# Superseal.net
KiCad netlist of a schematic drawn in Altium Designer
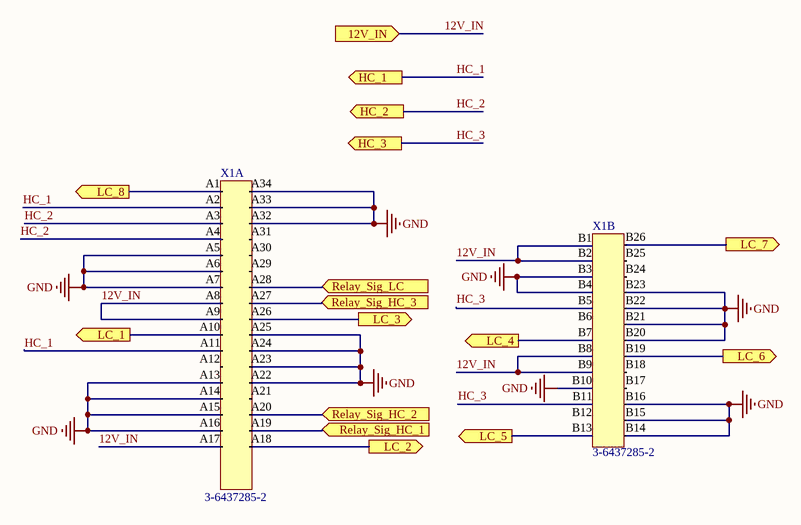
[diagram p0: Superseal.SchDoc]

(export (version "E")
  (design (tool "Eeschema 10.0.6"))
  (components
    (comp (ref "X1")
      (value "3-6437285-2")
      (footprint "SUPERSEAL 60POS 90Deg")
      (description "90 Degree")
      (libsource (lib "Altium-Lib") (part "CONN Superseal 60POS"))
    )
  )
  (nets
    (net (code "1") (name "/12V_IN") (class "Default")
      (node (ref "X1") (pin "A17") (pintype "bidirectional"))
      (node (ref "X1") (pin "A8") (pintype "bidirectional"))
      (node (ref "X1") (pin "A9") (pintype "bidirectional"))
      (node (ref "X1") (pin "B1") (pintype "bidirectional"))
      (node (ref "X1") (pin "B2") (pintype "bidirectional"))
      (node (ref "X1") (pin "B8") (pintype "bidirectional"))
      (node (ref "X1") (pin "B9") (pintype "bidirectional"))
    )
    (net (code "2") (name "/HC_1") (class "Default")
      (node (ref "X1") (pin "A11") (pintype "bidirectional"))
      (node (ref "X1") (pin "A2") (pintype "bidirectional"))
    )
    (net (code "3") (name "/HC_2") (class "Default")
      (node (ref "X1") (pin "A3") (pintype "bidirectional"))
      (node (ref "X1") (pin "A4") (pintype "bidirectional"))
    )
    (net (code "4") (name "/HC_3") (class "Default")
      (node (ref "X1") (pin "B11") (pintype "bidirectional"))
      (node (ref "X1") (pin "B5") (pintype "bidirectional"))
    )
    (net (code "5") (name "/LC_1") (class "Default") (node (ref "X1") (pin "A10") (pintype "bidirectional")))
    (net (code "6") (name "/LC_2") (class "Default") (node (ref "X1") (pin "A18") (pintype "bidirectional")))
    (net (code "7") (name "/LC_3") (class "Default") (node (ref "X1") (pin "A26") (pintype "bidirectional")))
    (net (code "8") (name "/LC_4") (class "Default") (node (ref "X1") (pin "B7") (pintype "bidirectional")))
    (net (code "9") (name "/LC_5") (class "Default") (node (ref "X1") (pin "B13") (pintype "bidirectional")))
    (net (code "10") (name "/LC_6") (class "Default") (node (ref "X1") (pin "B19") (pintype "bidirectional")))
    (net (code "11") (name "/LC_7") (class "Default") (node (ref "X1") (pin "B26") (pintype "bidirectional")))
    (net (code "12") (name "/LC_8") (class "Default") (node (ref "X1") (pin "A1") (pintype "bidirectional")))
    (net (code "13") (name "/Relay_Sig_HC_1") (class "Default")
      (node (ref "X1") (pin "A19") (pintype "bidirectional"))
    )
    (net (code "14") (name "/Relay_Sig_HC_2") (class "Default")
      (node (ref "X1") (pin "A20") (pintype "bidirectional"))
    )
    (net (code "15") (name "/Relay_Sig_HC_3") (class "Default")
      (node (ref "X1") (pin "A27") (pintype "bidirectional"))
    )
    (net (code "16") (name "/Relay_Sig_LC") (class "Default")
      (node (ref "X1") (pin "A28") (pintype "bidirectional"))
    )
    (net (code "17") (name "GND") (class "Default")
      (node (ref "X1") (pin "A13") (pintype "bidirectional"))
      (node (ref "X1") (pin "A14") (pintype "bidirectional"))
      (node (ref "X1") (pin "A15") (pintype "bidirectional"))
      (node (ref "X1") (pin "A16") (pintype "bidirectional"))
      (node (ref "X1") (pin "A22") (pintype "bidirectional"))
      (node (ref "X1") (pin "A23") (pintype "bidirectional"))
      (node (ref "X1") (pin "A24") (pintype "bidirectional"))
      (node (ref "X1") (pin "A25") (pintype "bidirectional"))
      (node (ref "X1") (pin "A32") (pintype "bidirectional"))
      (node (ref "X1") (pin "A33") (pintype "bidirectional"))
      (node (ref "X1") (pin "A34") (pintype "bidirectional"))
      (node (ref "X1") (pin "A5") (pintype "bidirectional"))
      (node (ref "X1") (pin "A6") (pintype "bidirectional"))
      (node (ref "X1") (pin "A7") (pintype "bidirectional"))
      (node (ref "X1") (pin "B10") (pintype "bidirectional"))
      (node (ref "X1") (pin "B14") (pintype "bidirectional"))
      (node (ref "X1") (pin "B15") (pintype "bidirectional"))
      (node (ref "X1") (pin "B16") (pintype "bidirectional"))
      (node (ref "X1") (pin "B20") (pintype "bidirectional"))
      (node (ref "X1") (pin "B21") (pintype "bidirectional"))
      (node (ref "X1") (pin "B22") (pintype "bidirectional"))
      (node (ref "X1") (pin "B23") (pintype "bidirectional"))
      (node (ref "X1") (pin "B3") (pintype "bidirectional"))
      (node (ref "X1") (pin "B4") (pintype "bidirectional"))
    )
    (net (code "18") (name "unconnected-(X1-PadA12)") (class "Default")
      (node (ref "X1") (pin "A12") (pintype "bidirectional"))
    )
    (net (code "19") (name "unconnected-(X1-PadA21)") (class "Default")
      (node (ref "X1") (pin "A21") (pintype "bidirectional"))
    )
    (net (code "20") (name "unconnected-(X1-PadA29)") (class "Default")
      (node (ref "X1") (pin "A29") (pintype "bidirectional"))
    )
    (net (code "21") (name "unconnected-(X1-PadA30)") (class "Default")
      (node (ref "X1") (pin "A30") (pintype "bidirectional"))
    )
    (net (code "22") (name "unconnected-(X1-PadA31)") (class "Default")
      (node (ref "X1") (pin "A31") (pintype "bidirectional"))
    )
    (net (code "23") (name "unconnected-(X1-PadB6)") (class "Default")
      (node (ref "X1") (pin "B6") (pintype "bidirectional"))
    )
    (net (code "24") (name "unconnected-(X1-PadB12)") (class "Default")
      (node (ref "X1") (pin "B12") (pintype "bidirectional"))
    )
    (net (code "25") (name "unconnected-(X1-PadB17)") (class "Default")
      (node (ref "X1") (pin "B17") (pintype "bidirectional"))
    )
    (net (code "26") (name "unconnected-(X1-PadB18)") (class "Default")
      (node (ref "X1") (pin "B18") (pintype "bidirectional"))
    )
    (net (code "27") (name "unconnected-(X1-PadB24)") (class "Default")
      (node (ref "X1") (pin "B24") (pintype "bidirectional"))
    )
    (net (code "28") (name "unconnected-(X1-PadB25)") (class "Default")
      (node (ref "X1") (pin "B25") (pintype "bidirectional"))
    )
  )
)
